# The_Flying_Jalapeno.net
KiCad netlist of a schematic drawn in EAGLE
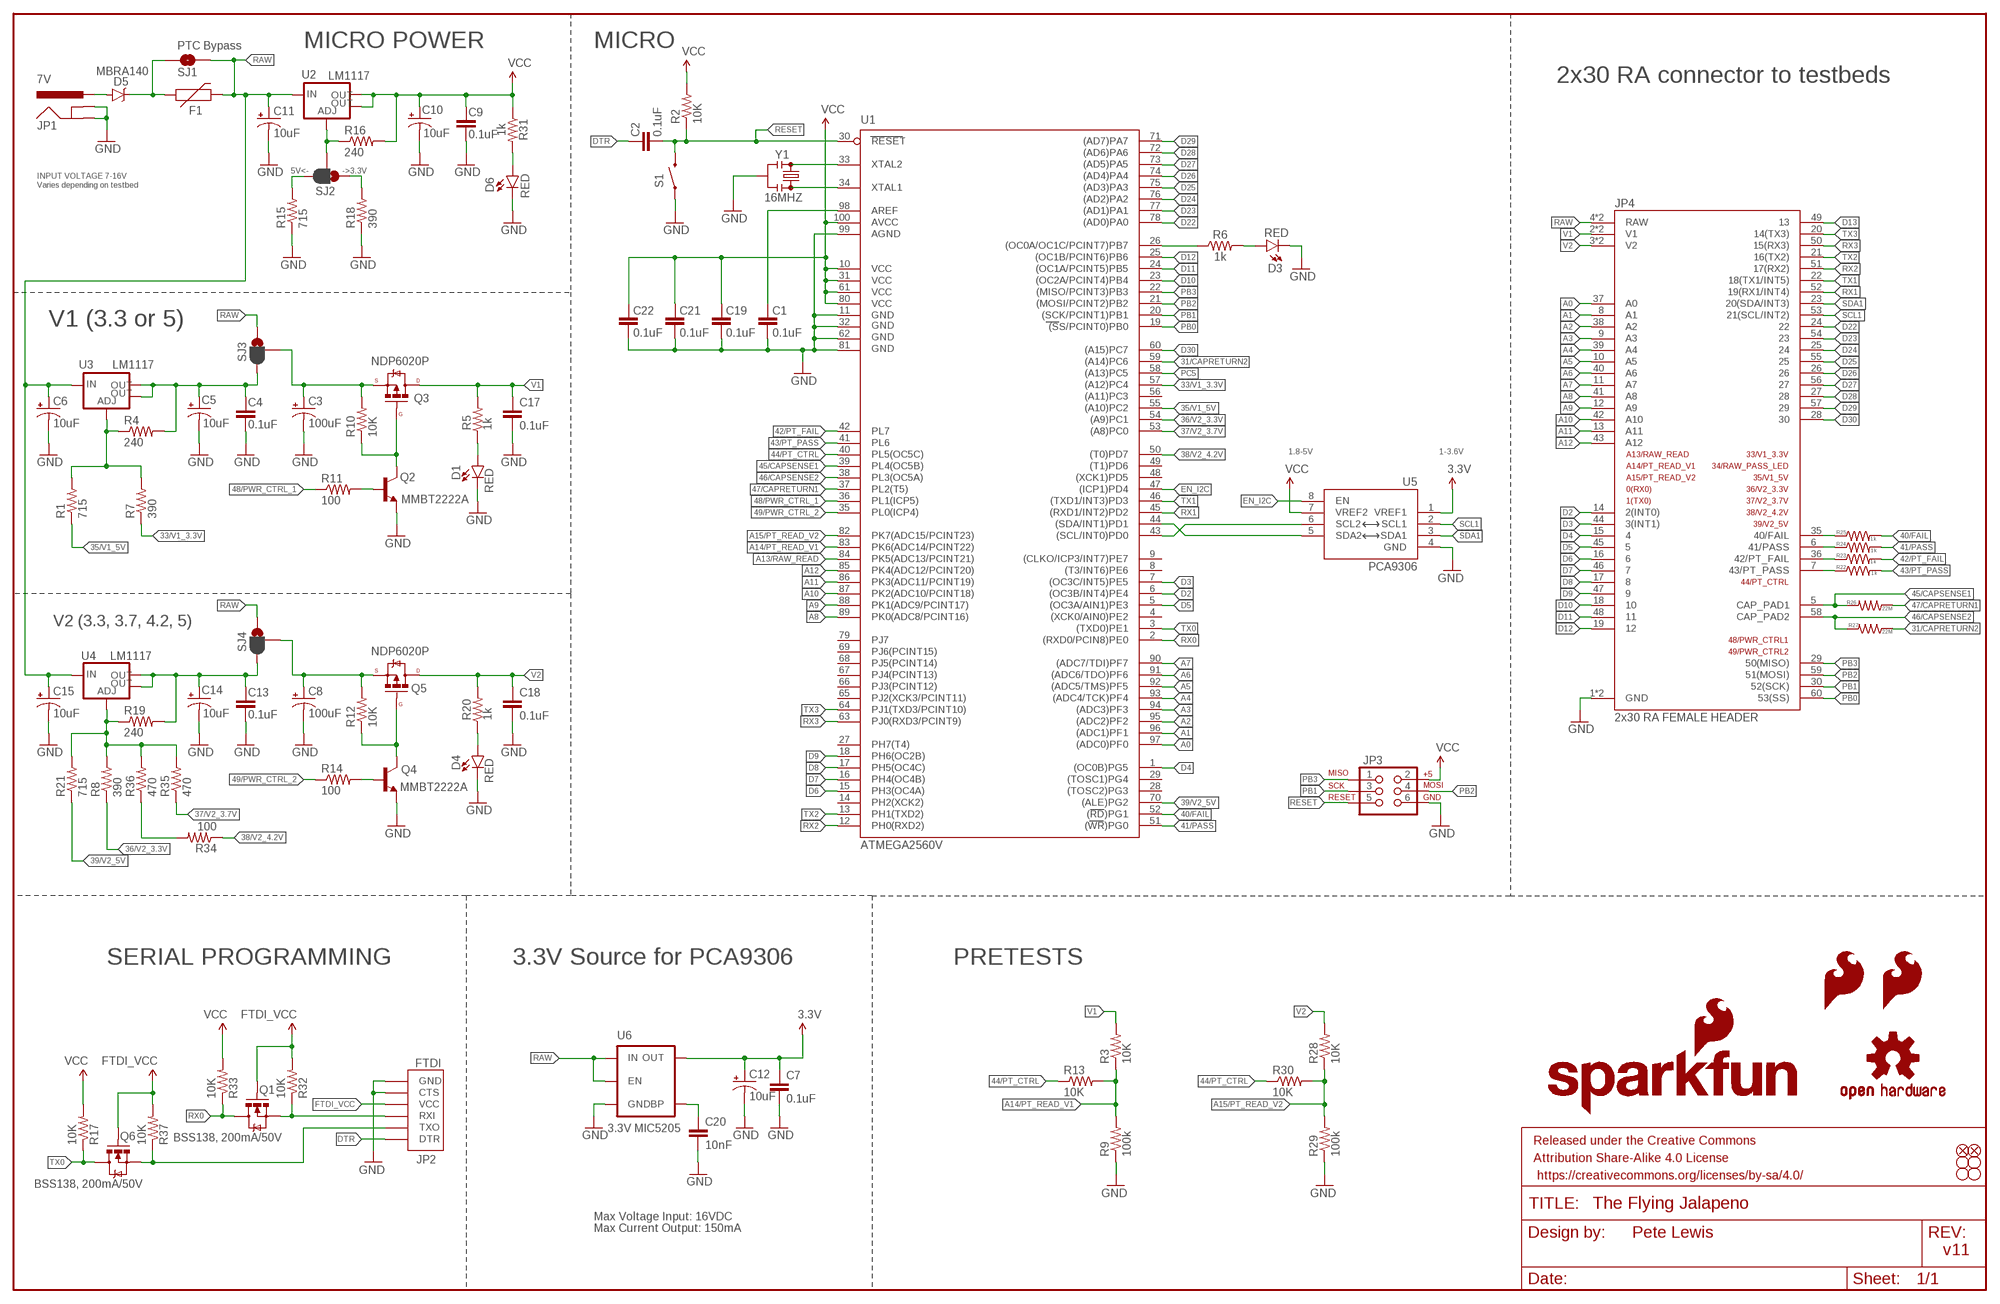
[diagram p0: schematic, sheet 1]

(export (version "E")
  (design (tool "Eeschema 10.0.6"))
  (components
    (comp (ref "C1")
      (value "0.1uF")
      (footprint "eagle-import:0603-CAP")
      (libsource (lib "eagle-import") (part "0.1UF-25V(+80/-20%)(0603)"))
    )
    (comp (ref "C2")
      (value "0.1uF")
      (footprint "eagle-import:0603-CAP")
      (libsource (lib "eagle-import") (part "0.1UF-25V(+80/-20%)(0603)"))
    )
    (comp (ref "C3")
      (value "100uF")
      (footprint "eagle-import:NIC_10X10.5_CAP")
      (libsource (lib "eagle-import") (part "100UF-63V-20%(ELECT)"))
    )
    (comp (ref "C4")
      (value "0.1uF")
      (footprint "eagle-import:0603-CAP")
      (libsource (lib "eagle-import") (part "0.1UF-25V(+80/-20%)(0603)"))
    )
    (comp (ref "C5")
      (value "10uF")
      (footprint "eagle-import:EIA3216")
      (libsource (lib "eagle-import") (part "10UF-16V-10%(TANT)"))
    )
    (comp (ref "C6")
      (value "10uF")
      (footprint "eagle-import:EIA3216")
      (libsource (lib "eagle-import") (part "10UF-16V-10%(TANT)"))
    )
    (comp (ref "C7")
      (value "0.1uF")
      (footprint "eagle-import:0603-CAP")
      (libsource (lib "eagle-import") (part "0.1UF-25V(+80/-20%)(0603)"))
    )
    (comp (ref "C8")
      (value "100uF")
      (footprint "eagle-import:NIC_10X10.5_CAP")
      (libsource (lib "eagle-import") (part "100UF-63V-20%(ELECT)"))
    )
    (comp (ref "C9")
      (value "0.1uF")
      (footprint "eagle-import:0603-CAP")
      (libsource (lib "eagle-import") (part "0.1UF-25V(+80/-20%)(0603)"))
    )
    (comp (ref "C10")
      (value "10uF")
      (footprint "eagle-import:EIA3216")
      (libsource (lib "eagle-import") (part "10UF-16V-10%(TANT)"))
    )
    (comp (ref "C11")
      (value "10uF")
      (footprint "eagle-import:EIA3216")
      (libsource (lib "eagle-import") (part "10UF-16V-10%(TANT)"))
    )
    (comp (ref "C12")
      (value "10uF")
      (footprint "eagle-import:0603-POL")
      (libsource (lib "eagle-import") (part "10UF-6.3V-20%(0603)(TANT){dblquote}"))
    )
    (comp (ref "C13")
      (value "0.1uF")
      (footprint "eagle-import:0603-CAP")
      (libsource (lib "eagle-import") (part "0.1UF-25V(+80/-20%)(0603)"))
    )
    (comp (ref "C14")
      (value "10uF")
      (footprint "eagle-import:EIA3216")
      (libsource (lib "eagle-import") (part "10UF-16V-10%(TANT)"))
    )
    (comp (ref "C15")
      (value "10uF")
      (footprint "eagle-import:EIA3216")
      (libsource (lib "eagle-import") (part "10UF-16V-10%(TANT)"))
    )
    (comp (ref "C17")
      (value "0.1uF")
      (footprint "eagle-import:0603-CAP")
      (libsource (lib "eagle-import") (part "0.1UF-25V(+80/-20%)(0603)"))
    )
    (comp (ref "C18")
      (value "0.1uF")
      (footprint "eagle-import:0603-CAP")
      (libsource (lib "eagle-import") (part "0.1UF-25V(+80/-20%)(0603)"))
    )
    (comp (ref "C19")
      (value "0.1uF")
      (footprint "eagle-import:0603-CAP")
      (libsource (lib "eagle-import") (part "0.1UF-25V(+80/-20%)(0603)"))
    )
    (comp (ref "C20")
      (value "10nF")
      (footprint "eagle-import:0603")
      (libsource (lib "eagle-import") (part "10NF-0603-50V-10%"))
    )
    (comp (ref "C21")
      (value "0.1uF")
      (footprint "eagle-import:0603-CAP")
      (libsource (lib "eagle-import") (part "0.1UF-25V(+80/-20%)(0603)"))
    )
    (comp (ref "C22")
      (value "0.1uF")
      (footprint "eagle-import:0603-CAP")
      (libsource (lib "eagle-import") (part "0.1UF-25V(+80/-20%)(0603)"))
    )
    (comp (ref "D1")
      (value "RED")
      (footprint "eagle-import:LED-1206")
      (libsource (lib "eagle-import") (part "LED-RED1206"))
    )
    (comp (ref "D3")
      (value "RED")
      (footprint "eagle-import:LED-1206")
      (libsource (lib "eagle-import") (part "LED-RED1206"))
    )
    (comp (ref "D4")
      (value "RED")
      (footprint "eagle-import:LED-1206")
      (libsource (lib "eagle-import") (part "LED-RED1206"))
    )
    (comp (ref "D5")
      (value "MBRA140")
      (footprint "eagle-import:SMA-DIODE")
      (libsource (lib "eagle-import") (part "DIODE-SCHOTTKY-MBRA140"))
    )
    (comp (ref "D6")
      (value "RED")
      (footprint "eagle-import:LED-1206")
      (libsource (lib "eagle-import") (part "LED-RED1206"))
    )
    (comp (ref "F1")
      (value "PTCTHERMISTOR1206")
      (footprint "eagle-import:PTC-1206")
      (libsource (lib "eagle-import") (part "PTCTHERMISTOR1206"))
    )
    (comp (ref "FRAME1")
      (value "FRAME-LEDGER")
      (footprint "eagle-import:CREATIVE_COMMONS")
      (libsource (lib "eagle-import") (part "FRAME-LEDGER"))
    )
    (comp (ref "JP1")
      (value "7V")
      (footprint "eagle-import:POWER_JACK_PTH_LOCK")
      (libsource (lib "eagle-import") (part "POWER_JACKPTH_LOCK"))
    )
    (comp (ref "JP2")
      (value "FTDI")
      (footprint "eagle-import:FTDI_DEVICE_RA_SMT")
      (libsource (lib "eagle-import") (part "FTDI_BASIC_DEVICE_SIDERA_SMT"))
    )
    (comp (ref "JP3")
      (value "AVR_SPI_PRG_6PTH")
      (footprint "eagle-import:2X3")
      (libsource (lib "eagle-import") (part "AVR_SPI_PRG_6PTH"))
    )
    (comp (ref "JP4")
      (value "2x30 RA FEMALE HEADER")
      (footprint "eagle-import:FLYING_JALAPENO_V3_F")
      (libsource (lib "eagle-import") (part "FLYING_JALAPENO_V3FEMALE"))
    )
    (comp (ref "JP5")
      (value "FIDUCIALUFIDUCIAL")
      (footprint "eagle-import:MICRO-FIDUCIAL")
      (libsource (lib "eagle-import") (part "FIDUCIALUFIDUCIAL"))
    )
    (comp (ref "JP8")
      (value "FIDUCIALUFIDUCIAL")
      (footprint "eagle-import:MICRO-FIDUCIAL")
      (libsource (lib "eagle-import") (part "FIDUCIALUFIDUCIAL"))
    )
    (comp (ref "LOGO1")
      (value "SFE_LOGO_NAME_FLAME.5_INCH")
      (footprint "eagle-import:SFE_LOGO_NAME_FLAME_.5")
      (libsource (lib "eagle-import") (part "SFE_LOGO_NAME_FLAME.5_INCH"))
    )
    (comp (ref "LOGO2")
      (value "SFE_LOGO_FLAME.3_INCH")
      (footprint "eagle-import:SFE_LOGO_FLAME_.3")
      (libsource (lib "eagle-import") (part "SFE_LOGO_FLAME.3_INCH"))
    )
    (comp (ref "LOGO3")
      (value "SFE_LOGO_FLAME.1_INCH")
      (footprint "eagle-import:SFE_LOGO_FLAME_.1")
      (libsource (lib "eagle-import") (part "SFE_LOGO_FLAME.1_INCH"))
    )
    (comp (ref "LOGO4")
      (value "OSHW-LOGOL")
      (footprint "eagle-import:OSHW-LOGO-L")
      (libsource (lib "eagle-import") (part "OSHW-LOGOL"))
    )
    (comp (ref "Q1")
      (value "BSS138, 200mA/50V")
      (footprint "eagle-import:SOT23-3")
      (libsource (lib "eagle-import") (part "MOSFET-NCHANNELBSS138"))
    )
    (comp (ref "Q2")
      (value "MMBT2222A")
      (footprint "eagle-import:SOT23-3")
      (libsource (lib "eagle-import") (part "TRANSISTOR_NPNMMBT2222A"))
    )
    (comp (ref "Q3")
      (value "NDP6020P")
      (footprint "eagle-import:TO220V")
      (libsource (lib "eagle-import") (part "MOSFET-PCHANNELNDP6020P_20V_24A_LOW_VGS_TH"))
    )
    (comp (ref "Q4")
      (value "MMBT2222A")
      (footprint "eagle-import:SOT23-3")
      (libsource (lib "eagle-import") (part "TRANSISTOR_NPNMMBT2222A"))
    )
    (comp (ref "Q5")
      (value "NDP6020P")
      (footprint "eagle-import:TO220V")
      (libsource (lib "eagle-import") (part "MOSFET-PCHANNELNDP6020P_20V_24A_LOW_VGS_TH"))
    )
    (comp (ref "Q6")
      (value "BSS138, 200mA/50V")
      (footprint "eagle-import:SOT23-3")
      (libsource (lib "eagle-import") (part "MOSFET-NCHANNELBSS138"))
    )
    (comp (ref "R1")
      (value "715")
      (footprint "eagle-import:0603-RES")
      (libsource (lib "eagle-import") (part "715OHM1/10W1%(0603)"))
    )
    (comp (ref "R2")
      (value "10K")
      (footprint "eagle-import:0603-RES")
      (libsource (lib "eagle-import") (part "10KOHM-1/10W-1%(0603)0603"))
    )
    (comp (ref "R3")
      (value "10K")
      (footprint "eagle-import:0603-RES")
      (libsource (lib "eagle-import") (part "10KOHM-1/10W-1%(0603)0603"))
    )
    (comp (ref "R4")
      (value "240")
      (footprint "eagle-import:0603-RES")
      (libsource (lib "eagle-import") (part "240OHM1/10W1%(0603)"))
    )
    (comp (ref "R5")
      (value "1k")
      (footprint "eagle-import:0603")
      (libsource (lib "eagle-import") (part "1KOHM-0603-1/10W-1%"))
    )
    (comp (ref "R6")
      (value "1k")
      (footprint "eagle-import:0603")
      (libsource (lib "eagle-import") (part "1KOHM-0603-1/10W-1%"))
    )
    (comp (ref "R7")
      (value "390")
      (footprint "eagle-import:0603-RES")
      (libsource (lib "eagle-import") (part "390OHM1/10W1%(0603)"))
    )
    (comp (ref "R8")
      (value "390")
      (footprint "eagle-import:0603-RES")
      (libsource (lib "eagle-import") (part "390OHM1/10W1%(0603)"))
    )
    (comp (ref "R9")
      (value "100k")
      (footprint "eagle-import:0603-RES")
      (libsource (lib "eagle-import") (part "100KOHM-1/10W-1%(0603)"))
    )
    (comp (ref "R10")
      (value "10K")
      (footprint "eagle-import:0603-RES")
      (libsource (lib "eagle-import") (part "10KOHM-1/10W-1%(0603)0603"))
    )
    (comp (ref "R11")
      (value "100")
      (footprint "eagle-import:0603-RES")
      (libsource (lib "eagle-import") (part "100OHM-1/10W-1%(0603)"))
    )
    (comp (ref "R12")
      (value "10K")
      (footprint "eagle-import:0603-RES")
      (libsource (lib "eagle-import") (part "10KOHM-1/10W-1%(0603)0603"))
    )
    (comp (ref "R13")
      (value "10K")
      (footprint "eagle-import:0603-RES")
      (libsource (lib "eagle-import") (part "10KOHM-1/10W-1%(0603)0603"))
    )
    (comp (ref "R14")
      (value "100")
      (footprint "eagle-import:0603-RES")
      (libsource (lib "eagle-import") (part "100OHM-1/10W-1%(0603)"))
    )
    (comp (ref "R15")
      (value "715")
      (footprint "eagle-import:0603-RES")
      (libsource (lib "eagle-import") (part "715OHM1/10W1%(0603)"))
    )
    (comp (ref "R16")
      (value "240")
      (footprint "eagle-import:0603-RES")
      (libsource (lib "eagle-import") (part "240OHM1/10W1%(0603)"))
    )
    (comp (ref "R17")
      (value "10K")
      (footprint "eagle-import:0603-RES")
      (libsource (lib "eagle-import") (part "10KOHM-1/10W-1%(0603)0603"))
    )
    (comp (ref "R18")
      (value "390")
      (footprint "eagle-import:0603-RES")
      (libsource (lib "eagle-import") (part "390OHM1/10W1%(0603)"))
    )
    (comp (ref "R19")
      (value "240")
      (footprint "eagle-import:0603-RES")
      (libsource (lib "eagle-import") (part "240OHM1/10W1%(0603)"))
    )
    (comp (ref "R20")
      (value "1k")
      (footprint "eagle-import:0603")
      (libsource (lib "eagle-import") (part "1KOHM-0603-1/10W-1%"))
    )
    (comp (ref "R21")
      (value "715")
      (footprint "eagle-import:0603-RES")
      (libsource (lib "eagle-import") (part "715OHM1/10W1%(0603)"))
    )
    (comp (ref "R22")
      (value "1k")
      (footprint "eagle-import:0603")
      (libsource (lib "eagle-import") (part "1KOHM-0603-1/10W-1%"))
    )
    (comp (ref "R23")
      (value "1k")
      (footprint "eagle-import:0603")
      (libsource (lib "eagle-import") (part "1KOHM-0603-1/10W-1%"))
    )
    (comp (ref "R24")
      (value "1k")
      (footprint "eagle-import:0603")
      (libsource (lib "eagle-import") (part "1KOHM-0603-1/10W-1%"))
    )
    (comp (ref "R25")
      (value "1k")
      (footprint "eagle-import:0603")
      (libsource (lib "eagle-import") (part "1KOHM-0603-1/10W-1%"))
    )
    (comp (ref "R26")
      (value "22M")
      (footprint "eagle-import:0603-RES")
      (libsource (lib "eagle-import") (part "22MOHM-1/10W-10%(0603)"))
    )
    (comp (ref "R27")
      (value "22M")
      (footprint "eagle-import:0603-RES")
      (libsource (lib "eagle-import") (part "22MOHM-1/10W-10%(0603)"))
    )
    (comp (ref "R28")
      (value "10K")
      (footprint "eagle-import:0603-RES")
      (libsource (lib "eagle-import") (part "10KOHM-1/10W-1%(0603)0603"))
    )
    (comp (ref "R29")
      (value "100k")
      (footprint "eagle-import:0603-RES")
      (libsource (lib "eagle-import") (part "100KOHM-1/10W-1%(0603)"))
    )
    (comp (ref "R30")
      (value "10K")
      (footprint "eagle-import:0603-RES")
      (libsource (lib "eagle-import") (part "10KOHM-1/10W-1%(0603)0603"))
    )
    (comp (ref "R31")
      (value "1k")
      (footprint "eagle-import:0603")
      (libsource (lib "eagle-import") (part "1KOHM-0603-1/10W-1%"))
    )
    (comp (ref "R32")
      (value "10K")
      (footprint "eagle-import:0603-RES")
      (libsource (lib "eagle-import") (part "10KOHM-1/10W-1%(0603)0603"))
    )
    (comp (ref "R33")
      (value "10K")
      (footprint "eagle-import:0603-RES")
      (libsource (lib "eagle-import") (part "10KOHM-1/10W-1%(0603)0603"))
    )
    (comp (ref "R34")
      (value "100")
      (footprint "eagle-import:0603-RES")
      (libsource (lib "eagle-import") (part "100OHM-1/10W-1%(0603)"))
    )
    (comp (ref "R35")
      (value "470")
      (footprint "eagle-import:0603-RES")
      (libsource (lib "eagle-import") (part "470OHM1/10W1%(0603)"))
    )
    (comp (ref "R36")
      (value "470")
      (footprint "eagle-import:0603-RES")
      (libsource (lib "eagle-import") (part "470OHM1/10W1%(0603)"))
    )
    (comp (ref "R37")
      (value "10K")
      (footprint "eagle-import:0603-RES")
      (libsource (lib "eagle-import") (part "10KOHM-1/10W-1%(0603)0603"))
    )
    (comp (ref "S1")
      (value "SWITCH-MOMENTARY-2SMD-REDUNDANT")
      (footprint "eagle-import:TACTILE-SWITCH-SMD")
      (libsource (lib "eagle-import") (part "SWITCH-MOMENTARY-2SMD-REDUNDANT"))
    )
    (comp (ref "SJ1")
      (value "PTC Bypass")
      (footprint "eagle-import:PAD-JUMPER-2-NO_NO_SILK")
      (libsource (lib "eagle-import") (part "JUMPER-PAD-2-NO"))
    )
    (comp (ref "SJ2")
      (value "JUMPER-PAD-3-2OF3_NC_BY_PASTE")
      (footprint "eagle-import:PAD-JUMPER-3-2OF3_NC_BY_PASTE_YES_SILK_FULL_BOX")
      (libsource (lib "eagle-import") (part "JUMPER-PAD-3-2OF3_NC_BY_PASTE"))
    )
    (comp (ref "SJ3")
      (value "JUMPER-PAD-3-2OF3_NC_BY_PASTE")
      (footprint "eagle-import:PAD-JUMPER-3-2OF3_NC_BY_PASTE_YES_SILK_FULL_BOX")
      (libsource (lib "eagle-import") (part "JUMPER-PAD-3-2OF3_NC_BY_PASTE"))
    )
    (comp (ref "SJ4")
      (value "JUMPER-PAD-3-2OF3_NC_BY_PASTE")
      (footprint "eagle-import:PAD-JUMPER-3-2OF3_NC_BY_PASTE_YES_SILK_FULL_BOX")
      (libsource (lib "eagle-import") (part "JUMPER-PAD-3-2OF3_NC_BY_PASTE"))
    )
    (comp (ref "STANDOFF1")
      (value "STAND-OFFTIGHT")
      (footprint "eagle-import:STAND-OFF-TIGHT")
      (libsource (lib "eagle-import") (part "STAND-OFFTIGHT"))
    )
    (comp (ref "STANDOFF2")
      (value "STAND-OFFTIGHT")
      (footprint "eagle-import:STAND-OFF-TIGHT")
      (libsource (lib "eagle-import") (part "STAND-OFFTIGHT"))
    )
    (comp (ref "STANDOFF3")
      (value "STAND-OFFTIGHT")
      (footprint "eagle-import:STAND-OFF-TIGHT")
      (libsource (lib "eagle-import") (part "STAND-OFFTIGHT"))
    )
    (comp (ref "STANDOFF4")
      (value "STAND-OFFTIGHT")
      (footprint "eagle-import:STAND-OFF-TIGHT")
      (libsource (lib "eagle-import") (part "STAND-OFFTIGHT"))
    )
    (comp (ref "U1")
      (value "ATMEGA2560AU")
      (footprint "eagle-import:TQFP100")
      (libsource (lib "eagle-import") (part "ATMEGA2560AU"))
    )
    (comp (ref "U2")
      (value "LM1117")
      (footprint "eagle-import:SOT223")
      (libsource (lib "eagle-import") (part "V_REG_LM1117SOT223"))
    )
    (comp (ref "U3")
      (value "LM1117")
      (footprint "eagle-import:SOT223")
      (libsource (lib "eagle-import") (part "V_REG_LM1117SOT223"))
    )
    (comp (ref "U4")
      (value "LM1117")
      (footprint "eagle-import:SOT223")
      (libsource (lib "eagle-import") (part "V_REG_LM1117SOT223"))
    )
    (comp (ref "U5")
      (value "PCA9306")
      (footprint "eagle-import:PCA9306DC-1_1")
      (libsource (lib "eagle-import") (part "PCA9306PCA9306DC-1{colon}1"))
    )
    (comp (ref "U6")
      (value "3.3V MIC5205")
      (footprint "eagle-import:SOT23-5")
      (libsource (lib "eagle-import") (part "MIC52053.3V"))
    )
    (comp (ref "Y1")
      (value "16MHZ")
      (footprint "eagle-import:RESONATOR-SMD")
      (libsource (lib "eagle-import") (part "RESONATOR16MHZ"))
    )
  )
  (nets
    (net (code "1") (name "3.3V") (class "Default")
      (node (ref "C12") (pin "A") (pinfunction "+_A") (pintype "passive"))
      (node (ref "C7") (pin "1") (pinfunction "1_1") (pintype "passive"))
      (node (ref "U5") (pin "1") (pinfunction "VREF1_1") (pintype "bidirectional"))
      (node (ref "U6") (pin "5") (pinfunction "OUT_5") (pintype "passive"))
    )
    (net (code "2") (name "31{slash}CAPRETURN2") (class "Default")
      (node (ref "R27") (pin "1") (pinfunction "1_1") (pintype "passive"))
      (node (ref "U1") (pin "59") (pinfunction "(A14)PC6_59") (pintype "bidirectional"))
    )
    (net (code "3") (name "33{slash}V1_3.3V") (class "Default")
      (node (ref "R7") (pin "1") (pinfunction "1_1") (pintype "passive"))
      (node (ref "U1") (pin "57") (pinfunction "(A12)PC4_57") (pintype "bidirectional"))
    )
    (net (code "4") (name "35{slash}V1_5V") (class "Default")
      (node (ref "R1") (pin "1") (pinfunction "1_1") (pintype "passive"))
      (node (ref "U1") (pin "55") (pinfunction "(A10)PC2_55") (pintype "bidirectional"))
    )
    (net (code "5") (name "36{slash}V2_3.3V") (class "Default")
      (node (ref "R8") (pin "1") (pinfunction "1_1") (pintype "passive"))
      (node (ref "U1") (pin "54") (pinfunction "(A9)PC1_54") (pintype "bidirectional"))
    )
    (net (code "6") (name "37{slash}V2_3.7V") (class "Default")
      (node (ref "R35") (pin "1") (pinfunction "1_1") (pintype "passive"))
      (node (ref "U1") (pin "53") (pinfunction "(A8)PC0_53") (pintype "bidirectional"))
    )
    (net (code "7") (name "38{slash}V2_4.2V") (class "Default")
      (node (ref "R34") (pin "1") (pinfunction "1_1") (pintype "passive"))
      (node (ref "U1") (pin "50") (pinfunction "(T0)PD7_50") (pintype "bidirectional"))
    )
    (net (code "8") (name "39{slash}V2_5V") (class "Default")
      (node (ref "R21") (pin "1") (pinfunction "1_1") (pintype "passive"))
      (node (ref "U1") (pin "70") (pinfunction "(ALE)PG2_70") (pintype "bidirectional"))
    )
    (net (code "9") (name "40{slash}FAIL") (class "Default")
      (node (ref "R25") (pin "2") (pinfunction "2_2") (pintype "passive"))
      (node (ref "U1") (pin "52") (pinfunction "(RD)PG1_52") (pintype "bidirectional"))
    )
    (net (code "10") (name "41{slash}PASS") (class "Default")
      (node (ref "R24") (pin "2") (pinfunction "2_2") (pintype "passive"))
      (node (ref "U1") (pin "51") (pinfunction "(WR)PG0_51") (pintype "bidirectional"))
    )
    (net (code "11") (name "42{slash}PT_FAIL") (class "Default")
      (node (ref "R23") (pin "2") (pinfunction "2_2") (pintype "passive"))
      (node (ref "U1") (pin "42") (pinfunction "PL7_42") (pintype "bidirectional"))
    )
    (net (code "12") (name "43{slash}PT_PASS") (class "Default")
      (node (ref "R22") (pin "2") (pinfunction "2_2") (pintype "passive"))
      (node (ref "U1") (pin "41") (pinfunction "PL6_41") (pintype "bidirectional"))
    )
    (net (code "13") (name "44{slash}PT_CTRL") (class "Default")
      (node (ref "R13") (pin "1") (pinfunction "1_1") (pintype "passive"))
      (node (ref "R30") (pin "1") (pinfunction "1_1") (pintype "passive"))
      (node (ref "U1") (pin "40") (pinfunction "PL5(OC5C)_40") (pintype "bidirectional"))
    )
    (net (code "14") (name "45{slash}CAPSENSE1") (class "Default")
      (node (ref "JP4") (pin "5") (pinfunction "CAP_PAD1_5") (pintype "bidirectional"))
      (node (ref "R26") (pin "2") (pinfunction "2_2") (pintype "passive"))
      (node (ref "U1") (pin "39") (pinfunction "PL4(OC5B)_39") (pintype "bidirectional"))
    )
    (net (code "15") (name "46{slash}CAPSENSE2") (class "Default")
      (node (ref "JP4") (pin "58") (pinfunction "CAP_PAD2_58") (pintype "bidirectional"))
      (node (ref "R27") (pin "2") (pinfunction "2_2") (pintype "passive"))
      (node (ref "U1") (pin "38") (pinfunction "PL3(OC5A)_38") (pintype "bidirectional"))
    )
    (net (code "16") (name "47{slash}CAPRETURN1") (class "Default")
      (node (ref "R26") (pin "1") (pinfunction "1_1") (pintype "passive"))
      (node (ref "U1") (pin "37") (pinfunction "PL2(T5)_37") (pintype "bidirectional"))
    )
    (net (code "17") (name "48{slash}PWR_CTRL_1") (class "Default")
      (node (ref "R11") (pin "1") (pinfunction "1_1") (pintype "passive"))
      (node (ref "U1") (pin "36") (pinfunction "PL1(ICP5)_36") (pintype "bidirectional"))
    )
    (net (code "18") (name "49{slash}PWR_CTRL_2") (class "Default")
      (node (ref "R14") (pin "1") (pinfunction "1_1") (pintype "passive"))
      (node (ref "U1") (pin "35") (pinfunction "PL0(ICP4)_35") (pintype "bidirectional"))
    )
    (net (code "19") (name "A0") (class "Default")
      (node (ref "JP4") (pin "37") (pinfunction "A0_37") (pintype "bidirectional"))
      (node (ref "U1") (pin "97") (pinfunction "(ADC0)PF0_97") (pintype "bidirectional"))
    )
    (net (code "20") (name "A1") (class "Default")
      (node (ref "JP4") (pin "8") (pinfunction "A1_8") (pintype "bidirectional"))
      (node (ref "U1") (pin "96") (pinfunction "(ADC1)PF1_96") (pintype "bidirectional"))
    )
    (net (code "21") (name "A2") (class "Default")
      (node (ref "JP4") (pin "38") (pinfunction "A2_38") (pintype "bidirectional"))
      (node (ref "U1") (pin "95") (pinfunction "(ADC2)PF2_95") (pintype "bidirectional"))
    )
    (net (code "22") (name "A3") (class "Default")
      (node (ref "JP4") (pin "9") (pinfunction "A3_9") (pintype "bidirectional"))
      (node (ref "U1") (pin "94") (pinfunction "(ADC3)PF3_94") (pintype "bidirectional"))
    )
    (net (code "23") (name "A4") (class "Default")
      (node (ref "JP4") (pin "39") (pinfunction "A4_39") (pintype "bidirectional"))
      (node (ref "U1") (pin "93") (pinfunction "(ADC4/TCK)PF4_93") (pintype "bidirectional"))
    )
    (net (code "24") (name "A5") (class "Default")
      (node (ref "JP4") (pin "10") (pinfunction "A5_10") (pintype "bidirectional"))
      (node (ref "U1") (pin "92") (pinfunction "(ADC5/TMS)PF5_92") (pintype "bidirectional"))
    )
    (net (code "25") (name "A6") (class "Default")
      (node (ref "JP4") (pin "40") (pinfunction "A6_40") (pintype "bidirectional"))
      (node (ref "U1") (pin "91") (pinfunction "(ADC6/TDO)PF6_91") (pintype "bidirectional"))
    )
    (net (code "26") (name "A7") (class "Default")
      (node (ref "JP4") (pin "11") (pinfunction "A7_11") (pintype "bidirectional"))
      (node (ref "U1") (pin "90") (pinfunction "(ADC7/TDI)PF7_90") (pintype "bidirectional"))
    )
    (net (code "27") (name "A8") (class "Default")
      (node (ref "JP4") (pin "41") (pinfunction "A8_41") (pintype "bidirectional"))
      (node (ref "U1") (pin "89") (pinfunction "PK0(ADC8/PCINT16)_89") (pintype "bidirectional"))
    )
    (net (code "28") (name "A9") (class "Default")
      (node (ref "JP4") (pin "12") (pinfunction "A9_12") (pintype "bidirectional"))
      (node (ref "U1") (pin "88") (pinfunction "PK1(ADC9/PCINT17)_88") (pintype "bidirectional"))
    )
    (net (code "29") (name "A10") (class "Default")
      (node (ref "JP4") (pin "42") (pinfunction "A10_42") (pintype "bidirectional"))
      (node (ref "U1") (pin "87") (pinfunction "PK2(ADC10/PCINT18)_87") (pintype "bidirectional"))
    )
    (net (code "30") (name "A11") (class "Default")
      (node (ref "JP4") (pin "13") (pinfunction "A11_13") (pintype "bidirectional"))
      (node (ref "U1") (pin "86") (pinfunction "PK3(ADC11/PCINT19)_86") (pintype "bidirectional"))
    )
    (net (code "31") (name "A12") (class "Default")
      (node (ref "JP4") (pin "43") (pinfunction "A12_43") (pintype "bidirectional"))
      (node (ref "U1") (pin "85") (pinfunction "PK4(ADC12/PCINT20)_85") (pintype "bidirectional"))
    )
    (net (code "32") (name "A13{slash}RAW_READ") (class "Default")
      (node (ref "U1") (pin "84") (pinfunction "PK5(ADC13/PCINT21)_84") (pintype "bidirectional"))
    )
    (net (code "33") (name "A14{slash}PT_READ_V1") (class "Default")
      (node (ref "R13") (pin "2") (pinfunction "2_2") (pintype "passive"))
      (node (ref "R3") (pin "1") (pinfunction "1_1") (pintype "passive"))
      (node (ref "R9") (pin "2") (pinfunction "2_2") (pintype "passive"))
      (node (ref "U1") (pin "83") (pinfunction "PK6(ADC14/PCINT22)_83") (pintype "bidirectional"))
    )
    (net (code "34") (name "A15{slash}PT_READ_V2") (class "Default")
      (node (ref "R28") (pin "1") (pinfunction "1_1") (pintype "passive"))
      (node (ref "R29") (pin "2") (pinfunction "2_2") (pintype "passive"))
      (node (ref "R30") (pin "2") (pinfunction "2_2") (pintype "passive"))
      (node (ref "U1") (pin "82") (pinfunction "PK7(ADC15/PCINT23)_82") (pintype "bidirectional"))
    )
    (net (code "35") (name "D2") (class "Default")
      (node (ref "JP4") (pin "14") (pinfunction "2(INT0)_14") (pintype "bidirectional"))
      (node (ref "U1") (pin "6") (pinfunction "(OC3B/INT4)PE4_6") (pintype "bidirectional"))
    )
    (net (code "36") (name "D3") (class "Default")
      (node (ref "JP4") (pin "44") (pinfunction "3(INT1)_44") (pintype "bidirectional"))
      (node (ref "U1") (pin "7") (pinfunction "(OC3C/INT5)PE5_7") (pintype "bidirectional"))
    )
    (net (code "37") (name "D4") (class "Default")
      (node (ref "JP4") (pin "15") (pinfunction "4_15") (pintype "bidirectional"))
      (node (ref "U1") (pin "1") (pinfunction "(OC0B)PG5_1") (pintype "bidirectional"))
    )
    (net (code "38") (name "D5") (class "Default")
      (node (ref "JP4") (pin "45") (pinfunction "5_45") (pintype "bidirectional"))
      (node (ref "U1") (pin "5") (pinfunction "(OC3A/AIN1)PE3_5") (pintype "bidirectional"))
    )
    (net (code "39") (name "D6") (class "Default")
      (node (ref "JP4") (pin "16") (pinfunction "6_16") (pintype "bidirectional"))
      (node (ref "U1") (pin "15") (pinfunction "PH3(OC4A)_15") (pintype "bidirectional"))
    )
    (net (code "40") (name "D7") (class "Default")
      (node (ref "JP4") (pin "46") (pinfunction "7_46") (pintype "bidirectional"))
      (node (ref "U1") (pin "16") (pinfunction "PH4(OC4B)_16") (pintype "bidirectional"))
    )
    (net (code "41") (name "D8") (class "Default")
      (node (ref "JP4") (pin "17") (pinfunction "8_17") (pintype "bidirectional"))
      (node (ref "U1") (pin "17") (pinfunction "PH5(OC4C)_17") (pintype "bidirectional"))
    )
    (net (code "42") (name "D9") (class "Default")
      (node (ref "JP4") (pin "47") (pinfunction "9_47") (pintype "bidirectional"))
      (node (ref "U1") (pin "18") (pinfunction "PH6(OC2B)_18") (pintype "bidirectional"))
    )
    (net (code "43") (name "D10") (class "Default")
      (node (ref "JP4") (pin "18") (pinfunction "10_18") (pintype "bidirectional"))
      (node (ref "U1") (pin "23") (pinfunction "(OC2A/PCINT4)PB4_23") (pintype "bidirectional"))
    )
    (net (code "44") (name "D11") (class "Default")
      (node (ref "JP4") (pin "48") (pinfunction "11_48") (pintype "bidirectional"))
      (node (ref "U1") (pin "24") (pinfunction "(OC1A/PCINT5)PB5_24") (pintype "bidirectional"))
    )
    (net (code "45") (name "D12") (class "Default")
      (node (ref "JP4") (pin "19") (pinfunction "12_19") (pintype "bidirectional"))
      (node (ref "U1") (pin "25") (pinfunction "(OC1B/PCINT6)PB6_25") (pintype "bidirectional"))
    )
    (net (code "46") (name "D13") (class "Default")
      (node (ref "JP4") (pin "49") (pinfunction "13_49") (pintype "bidirectional"))
      (node (ref "R6") (pin "1") (pinfunction "1_1") (pintype "passive"))
      (node (ref "U1") (pin "26") (pinfunction "(OC0A/OC1C/PCINT7)PB7_26") (pintype "bidirectional"))
    )
    (net (code "47") (name "D22") (class "Default")
      (node (ref "JP4") (pin "24") (pinfunction "22_24") (pintype "bidirectional"))
      (node (ref "U1") (pin "78") (pinfunction "(AD0)PA0_78") (pintype "bidirectional"))
    )
    (net (code "48") (name "D23") (class "Default")
      (node (ref "JP4") (pin "54") (pinfunction "23_54") (pintype "bidirectional"))
      (node (ref "U1") (pin "77") (pinfunction "(AD1)PA1_77") (pintype "bidirectional"))
    )
    (net (code "49") (name "D24") (class "Default")
      (node (ref "JP4") (pin "25") (pinfunction "24_25") (pintype "bidirectional"))
      (node (ref "U1") (pin "76") (pinfunction "(AD2)PA2_76") (pintype "bidirectional"))
    )
    (net (code "50") (name "D25") (class "Default")
      (node (ref "JP4") (pin "55") (pinfunction "25_55") (pintype "bidirectional"))
      (node (ref "U1") (pin "75") (pinfunction "(AD3)PA3_75") (pintype "bidirectional"))
    )
    (net (code "51") (name "D26") (class "Default")
      (node (ref "JP4") (pin "26") (pinfunction "26_26") (pintype "bidirectional"))
      (node (ref "U1") (pin "74") (pinfunction "(AD4)PA4_74") (pintype "bidirectional"))
    )
    (net (code "52") (name "D27") (class "Default")
      (node (ref "JP4") (pin "56") (pinfunction "27_56") (pintype "bidirectional"))
      (node (ref "U1") (pin "73") (pinfunction "(AD5)PA5_73") (pintype "bidirectional"))
    )
    (net (code "53") (name "D28") (class "Default")
      (node (ref "JP4") (pin "27") (pinfunction "28_27") (pintype "bidirectional"))
      (node (ref "U1") (pin "72") (pinfunction "(AD6)PA6_72") (pintype "bidirectional"))
    )
    (net (code "54") (name "D29") (class "Default")
      (node (ref "JP4") (pin "57") (pinfunction "29_57") (pintype "bidirectional"))
      (node (ref "U1") (pin "71") (pinfunction "(AD7)PA7_71") (pintype "bidirectional"))
    )
    (net (code "55") (name "D30") (class "Default")
      (node (ref "JP4") (pin "28") (pinfunction "30_28") (pintype "bidirectional"))
      (node (ref "U1") (pin "60") (pinfunction "(A15)PC7_60") (pintype "bidirectional"))
    )
    (net (code "56") (name "DTR") (class "Default")
      (node (ref "C2") (pin "2") (pinfunction "2_2") (pintype "passive"))
      (node (ref "JP2") (pin "1") (pinfunction "DTR_1") (pintype "bidirectional"))
    )
    (net (code "57") (name "EN_I2C") (class "Default")
      (node (ref "U1") (pin "47") (pinfunction "(ICP1)PD4_47") (pintype "bidirectional"))
      (node (ref "U5") (pin "8") (pinfunction "EN_8") (pintype "bidirectional"))
    )
    (net (code "58") (name "FTDI_VCC") (class "Default")
      (node (ref "JP2") (pin "4") (pinfunction "VCC_4") (pintype "bidirectional"))
      (node (ref "Q1") (pin "1") (pinfunction "G_1") (pintype "passive"))
      (node (ref "Q6") (pin "1") (pinfunction "G_1") (pintype "passive"))
      (node (ref "R32") (pin "2") (pinfunction "2_2") (pintype "passive"))
      (node (ref "R37") (pin "2") (pinfunction "2_2") (pintype "passive"))
    )
    (net (code "59") (name "GND") (class "Default")
      (node (ref "C1") (pin "1") (pinfunction "1_1") (pintype "passive"))
      (node (ref "C10") (pin "C") (pinfunction "-_C") (pintype "passive"))
      (node (ref "C11") (pin "C") (pinfunction "-_C") (pintype "passive"))
      (node (ref "C12") (pin "K") (pinfunction "-_K") (pintype "passive"))
      (node (ref "C13") (pin "2") (pinfunction "2_2") (pintype "passive"))
      (node (ref "C14") (pin "C") (pinfunction "-_C") (pintype "passive"))
      (node (ref "C15") (pin "C") (pinfunction "-_C") (pintype "passive"))
      (node (ref "C17") (pin "2") (pinfunction "2_2") (pintype "passive"))
      (node (ref "C18") (pin "2") (pinfunction "2_2") (pintype "passive"))
      (node (ref "C19") (pin "1") (pinfunction "1_1") (pintype "passive"))
      (node (ref "C20") (pin "2") (pinfunction "2_2") (pintype "passive"))
      (node (ref "C21") (pin "1") (pinfunction "1_1") (pintype "passive"))
      (node (ref "C22") (pin "1") (pinfunction "1_1") (pintype "passive"))
      (node (ref "C3") (pin "-") (pinfunction "-_-") (pintype "passive"))
      (node (ref "C4") (pin "2") (pinfunction "2_2") (pintype "passive"))
      (node (ref "C5") (pin "C") (pinfunction "-_C") (pintype "passive"))
      (node (ref "C6") (pin "C") (pinfunction "-_C") (pintype "passive"))
      (node (ref "C7") (pin "2") (pinfunction "2_2") (pintype "passive"))
      (node (ref "C8") (pin "-") (pinfunction "-_-") (pintype "passive"))
      (node (ref "C9") (pin "2") (pinfunction "2_2") (pintype "passive"))
      (node (ref "D1") (pin "C") (pinfunction "C_C") (pintype "passive"))
      (node (ref "D3") (pin "C") (pinfunction "C_C") (pintype "passive"))
      (node (ref "D4") (pin "C") (pinfunction "C_C") (pintype "passive"))
      (node (ref "D6") (pin "C") (pinfunction "C_C") (pintype "passive"))
      (node (ref "JP1") (pin "GND") (pinfunction "GND_GND") (pintype "bidirectional"))
      (node (ref "JP1") (pin "GNDBREAK") (pinfunction "GNDBREAK_GNDBREAK") (pintype "bidirectional"))
      (node (ref "JP2") (pin "5") (pinfunction "CTS_5") (pintype "bidirectional"))
      (node (ref "JP2") (pin "6") (pinfunction "GND_6") (pintype "bidirectional"))
      (node (ref "JP3") (pin "6") (pinfunction "6_6") (pintype "passive"))
      (node (ref "JP4") (pin "1") (pinfunction "GND_1") (pintype "bidirectional"))
      (node (ref "JP4") (pin "31") (pinfunction "GND_31") (pintype "bidirectional"))
      (node (ref "Q2") (pin "2") (pinfunction "E_2") (pintype "passive"))
      (node (ref "Q4") (pin "2") (pinfunction "E_2") (pintype "passive"))
      (node (ref "R15") (pin "1") (pinfunction "1_1") (pintype "passive"))
      (node (ref "R18") (pin "1") (pinfunction "1_1") (pintype "passive"))
      (node (ref "R29") (pin "1") (pinfunction "1_1") (pintype "passive"))
      (node (ref "R9") (pin "1") (pinfunction "1_1") (pintype "passive"))
      (node (ref "S1") (pin "1") (pinfunction "1_1") (pintype "passive"))
      (node (ref "S1") (pin "2") (pinfunction "1_2") (pintype "passive"))
      (node (ref "U1") (pin "11") (pinfunction "GND_11") (pintype "power_in"))
      (node (ref "U1") (pin "32") (pinfunction "GND1_32") (pintype "power_in"))
      (node (ref "U1") (pin "62") (pinfunction "GND2_62") (pintype "power_in"))
      (node (ref "U1") (pin "81") (pinfunction "GND3_81") (pintype "power_in"))
      (node (ref "U1") (pin "99") (pinfunction "AGND_99") (pintype "power_in"))
      (node (ref "U5") (pin "4") (pinfunction "GND_4") (pintype "bidirectional"))
      (node (ref "U6") (pin "2") (pinfunction "GND_2") (pintype "input"))
      (node (ref "Y1") (pin "2") (pinfunction "2_2") (pintype "passive"))
    )
    (net (code "60") (name "Net-(C5-+)") (class "Default")
      (node (ref "C4") (pin "1") (pinfunction "1_1") (pintype "passive"))
      (node (ref "C5") (pin "A") (pinfunction "+_A") (pintype "passive"))
      (node (ref "R4") (pin "2") (pinfunction "2_2") (pintype "passive"))
      (node (ref "SJ3") (pin "3") (pinfunction "3_3") (pintype "passive"))
      (node (ref "U3") (pin "2") (pinfunction "OUT_2") (pintype "output"))
      (node (ref "U3") (pin "4") (pinfunction "OUT_4") (pintype "output"))
    )
    (net (code "61") (name "Net-(C14-+)") (class "Default")
      (node (ref "C13") (pin "1") (pinfunction "1_1") (pintype "passive"))
      (node (ref "C14") (pin "A") (pinfunction "+_A") (pintype "passive"))
      (node (ref "R19") (pin "2") (pinfunction "2_2") (pintype "passive"))
      (node (ref "SJ4") (pin "3") (pinfunction "3_3") (pintype "passive"))
      (node (ref "U4") (pin "2") (pinfunction "OUT_2") (pintype "output"))
      (node (ref "U4") (pin "4") (pinfunction "OUT_4") (pintype "output"))
    )
    (net (code "62") (name "Net-(D1-PadA)") (class "Default")
      (node (ref "D1") (pin "A") (pinfunction "A_A") (pintype "passive"))
      (node (ref "R5") (pin "1") (pinfunction "1_1") (pintype "passive"))
    )
    (net (code "63") (name "Net-(D3-PadA)") (class "Default")
      (node (ref "D3") (pin "A") (pinfunction "A_A") (pintype "passive"))
      (node (ref "R6") (pin "2") (pinfunction "2_2") (pintype "passive"))
    )
    (net (code "64") (name "Net-(D4-PadA)") (class "Default")
      (node (ref "D4") (pin "A") (pinfunction "A_A") (pintype "passive"))
      (node (ref "R20") (pin "1") (pinfunction "1_1") (pintype "passive"))
    )
    (net (code "65") (name "Net-(D5-PadA)") (class "Default")
      (node (ref "D5") (pin "A") (pinfunction "A_A") (pintype "passive"))
      (node (ref "JP1") (pin "PWR") (pinfunction "PWR_PWR") (pintype "bidirectional"))
    )
    (net (code "66") (name "Net-(D5-PadC)") (class "Default")
      (node (ref "D5") (pin "C") (pinfunction "C_C") (pintype "passive"))
      (node (ref "F1") (pin "1") (pinfunction "1_1") (pintype "bidirectional"))
      (node (ref "SJ1") (pin "1") (pinfunction "1_1") (pintype "passive"))
    )
    (net (code "67") (name "Net-(D6-PadA)") (class "Default")
      (node (ref "D6") (pin "A") (pinfunction "A_A") (pintype "passive"))
      (node (ref "R31") (pin "2") (pinfunction "2_2") (pintype "passive"))
    )
    (net (code "68") (name "Net-(JP2-RXI)") (class "Default")
      (node (ref "JP2") (pin "3") (pinfunction "RXI_3") (pintype "bidirectional"))
      (node (ref "Q1") (pin "2") (pinfunction "S_2") (pintype "passive"))
      (node (ref "R32") (pin "1") (pinfunction "1_1") (pintype "passive"))
    )
    (net (code "69") (name "Net-(JP2-TXO)") (class "Default")
      (node (ref "JP2") (pin "2") (pinfunction "TXO_2") (pintype "bidirectional"))
      (node (ref "Q6") (pin "2") (pinfunction "S_2") (pintype "passive"))
      (node (ref "R37") (pin "1") (pinfunction "1_1") (pintype "passive"))
    )
    (net (code "70") (name "Net-(JP4-40{slash}FAIL)") (class "Default")
      (node (ref "JP4") (pin "35") (pinfunction "40/FAIL_35") (pintype "bidirectional"))
      (node (ref "R25") (pin "1") (pinfunction "1_1") (pintype "passive"))
    )
    (net (code "71") (name "Net-(JP4-41{slash}PASS)") (class "Default")
      (node (ref "JP4") (pin "6") (pinfunction "41/PASS_6") (pintype "bidirectional"))
      (node (ref "R24") (pin "1") (pinfunction "1_1") (pintype "passive"))
    )
    (net (code "72") (name "Net-(JP4-42{slash}PT_FAIL)") (class "Default")
      (node (ref "JP4") (pin "36") (pinfunction "42/PT_FAIL_36") (pintype "bidirectional"))
      (node (ref "R23") (pin "1") (pinfunction "1_1") (pintype "passive"))
    )
    (net (code "73") (name "Net-(JP4-43{slash}PT_PASS)") (class "Default")
      (node (ref "JP4") (pin "7") (pinfunction "43/PT_PASS_7") (pintype "bidirectional"))
      (node (ref "R22") (pin "1") (pinfunction "1_1") (pintype "passive"))
    )
    (net (code "74") (name "Net-(Q2-B)") (class "Default")
      (node (ref "Q2") (pin "1") (pinfunction "B_1") (pintype "passive"))
      (node (ref "R11") (pin "2") (pinfunction "2_2") (pintype "passive"))
    )
    (net (code "75") (name "Net-(Q2-C)") (class "Default")
      (node (ref "Q2") (pin "3") (pinfunction "C_3") (pintype "passive"))
      (node (ref "Q3") (pin "1") (pinfunction "G_1") (pintype "passive"))
      (node (ref "R10") (pin "1") (pinfunction "1_1") (pintype "passive"))
    )
    (net (code "76") (name "Net-(Q3-S)") (class "Default")
      (node (ref "C3") (pin "+") (pinfunction "+_+") (pintype "passive"))
      (node (ref "Q3") (pin "3") (pinfunction "S_3") (pintype "passive"))
      (node (ref "R10") (pin "2") (pinfunction "2_2") (pintype "passive"))
      (node (ref "SJ3") (pin "2") (pinfunction "2_2") (pintype "passive"))
    )
    (net (code "77") (name "Net-(Q4-B)") (class "Default")
      (node (ref "Q4") (pin "1") (pinfunction "B_1") (pintype "passive"))
      (node (ref "R14") (pin "2") (pinfunction "2_2") (pintype "passive"))
    )
    (net (code "78") (name "Net-(Q4-C)") (class "Default")
      (node (ref "Q4") (pin "3") (pinfunction "C_3") (pintype "passive"))
      (node (ref "Q5") (pin "1") (pinfunction "G_1") (pintype "passive"))
      (node (ref "R12") (pin "1") (pinfunction "1_1") (pintype "passive"))
    )
    (net (code "79") (name "Net-(Q5-S)") (class "Default")
      (node (ref "C8") (pin "+") (pinfunction "+_+") (pintype "passive"))
      (node (ref "Q5") (pin "3") (pinfunction "S_3") (pintype "passive"))
      (node (ref "R12") (pin "2") (pinfunction "2_2") (pintype "passive"))
      (node (ref "SJ4") (pin "2") (pinfunction "2_2") (pintype "passive"))
    )
    (net (code "80") (name "Net-(R15-Pad2)") (class "Default")
      (node (ref "R15") (pin "2") (pinfunction "2_2") (pintype "passive"))
      (node (ref "SJ2") (pin "3") (pinfunction "3_3") (pintype "passive"))
    )
    (net (code "81") (name "Net-(R18-Pad2)") (class "Default")
      (node (ref "R18") (pin "2") (pinfunction "2_2") (pintype "passive"))
      (node (ref "SJ2") (pin "1") (pinfunction "1_1") (pintype "passive"))
    )
    (net (code "82") (name "Net-(R34-Pad2)") (class "Default")
      (node (ref "R34") (pin "2") (pinfunction "2_2") (pintype "passive"))
      (node (ref "R36") (pin "1") (pinfunction "1_1") (pintype "passive"))
    )
    (net (code "83") (name "Net-(U1-(SCL{slash}INT0)PD0)") (class "Default")
      (node (ref "U1") (pin "43") (pinfunction "(SCL/INT0)PD0_43") (pintype "bidirectional"))
      (node (ref "U5") (pin "6") (pinfunction "SCL2_6") (pintype "bidirectional"))
    )
    (net (code "84") (name "Net-(U1-(SDA{slash}INT1)PD1)") (class "Default")
      (node (ref "U1") (pin "44") (pinfunction "(SDA/INT1)PD1_44") (pintype "bidirectional"))
      (node (ref "U5") (pin "5") (pinfunction "SDA2_5") (pintype "bidirectional"))
    )
    (net (code "85") (name "Net-(U1-AREF)") (class "Default")
      (node (ref "C1") (pin "2") (pinfunction "2_2") (pintype "passive"))
      (node (ref "U1") (pin "98") (pinfunction "AREF_98") (pintype "bidirectional"))
    )
    (net (code "86") (name "Net-(U1-XTAL1)") (class "Default")
      (node (ref "U1") (pin "34") (pinfunction "XTAL1_34") (pintype "input"))
      (node (ref "Y1") (pin "1") (pinfunction "1_1") (pintype "passive"))
    )
    (net (code "87") (name "Net-(U1-XTAL2)") (class "Default")
      (node (ref "U1") (pin "33") (pinfunction "XTAL2_33") (pintype "output"))
      (node (ref "Y1") (pin "3") (pinfunction "3_3") (pintype "passive"))
    )
    (net (code "88") (name "Net-(U2-ADJ)") (class "Default")
      (node (ref "R16") (pin "1") (pinfunction "1_1") (pintype "passive"))
      (node (ref "SJ2") (pin "2") (pinfunction "2_2") (pintype "passive"))
      (node (ref "U2") (pin "1") (pinfunction "ADJ_1") (pintype "input"))
    )
    (net (code "89") (name "Net-(U3-ADJ)") (class "Default")
      (node (ref "R1") (pin "2") (pinfunction "2_2") (pintype "passive"))
      (node (ref "R4") (pin "1") (pinfunction "1_1") (pintype "passive"))
      (node (ref "R7") (pin "2") (pinfunction "2_2") (pintype "passive"))
      (node (ref "U3") (pin "1") (pinfunction "ADJ_1") (pintype "input"))
    )
    (net (code "90") (name "Net-(U4-ADJ)") (class "Default")
      (node (ref "R19") (pin "1") (pinfunction "1_1") (pintype "passive"))
      (node (ref "R21") (pin "2") (pinfunction "2_2") (pintype "passive"))
      (node (ref "R35") (pin "2") (pinfunction "2_2") (pintype "passive"))
      (node (ref "R36") (pin "2") (pinfunction "2_2") (pintype "passive"))
      (node (ref "R8") (pin "2") (pinfunction "2_2") (pintype "passive"))
      (node (ref "U4") (pin "1") (pinfunction "ADJ_1") (pintype "input"))
    )
    (net (code "91") (name "Net-(U6-BP)") (class "Default")
      (node (ref "C20") (pin "1") (pinfunction "1_1") (pintype "passive"))
      (node (ref "U6") (pin "4") (pinfunction "BP_4") (pintype "input"))
    )
    (net (code "92") (name "PB0") (class "Default")
      (node (ref "JP4") (pin "60") (pinfunction "53(SS)_60") (pintype "bidirectional"))
      (node (ref "U1") (pin "19") (pinfunction "(SS/PCINT0)PB0_19") (pintype "bidirectional"))
    )
    (net (code "93") (name "PB1") (class "Default")
      (node (ref "JP3") (pin "3") (pinfunction "3_3") (pintype "passive"))
      (node (ref "JP4") (pin "30") (pinfunction "52(SCK)_30") (pintype "bidirectional"))
      (node (ref "U1") (pin "20") (pinfunction "(SCK/PCINT1)PB1_20") (pintype "bidirectional"))
    )
    (net (code "94") (name "PB2") (class "Default")
      (node (ref "JP3") (pin "4") (pinfunction "4_4") (pintype "passive"))
      (node (ref "JP4") (pin "59") (pinfunction "51(MOSI)_59") (pintype "bidirectional"))
      (node (ref "U1") (pin "21") (pinfunction "(MOSI/PCINT2)PB2_21") (pintype "bidirectional"))
    )
    (net (code "95") (name "PB3") (class "Default")
      (node (ref "JP3") (pin "1") (pinfunction "1_1") (pintype "passive"))
      (node (ref "JP4") (pin "29") (pinfunction "50(MISO)_29") (pintype "bidirectional"))
      (node (ref "U1") (pin "22") (pinfunction "(MISO/PCINT3)PB3_22") (pintype "bidirectional"))
    )
    (net (code "96") (name "PC5") (class "Default")
      (node (ref "U1") (pin "58") (pinfunction "(A13)PC5_58") (pintype "bidirectional"))
    )
    (net (code "97") (name "RAW") (class "Default")
      (node (ref "C11") (pin "A") (pinfunction "+_A") (pintype "passive"))
      (node (ref "C15") (pin "A") (pinfunction "+_A") (pintype "passive"))
      (node (ref "C6") (pin "A") (pinfunction "+_A") (pintype "passive"))
      (node (ref "F1") (pin "2") (pinfunction "2_2") (pintype "bidirectional"))
      (node (ref "JP4") (pin "34") (pinfunction "RAW_34") (pintype "bidirectional"))
      (node (ref "JP4") (pin "4") (pinfunction "RAW_4") (pintype "bidirectional"))
      (node (ref "SJ1") (pin "2") (pinfunction "2_2") (pintype "passive"))
      (node (ref "SJ3") (pin "1") (pinfunction "1_1") (pintype "passive"))
      (node (ref "SJ4") (pin "1") (pinfunction "1_1") (pintype "passive"))
      (node (ref "U2") (pin "3") (pinfunction "IN_3") (pintype "input"))
      (node (ref "U3") (pin "3") (pinfunction "IN_3") (pintype "input"))
      (node (ref "U4") (pin "3") (pinfunction "IN_3") (pintype "input"))
      (node (ref "U6") (pin "1") (pinfunction "IN_1") (pintype "input"))
      (node (ref "U6") (pin "3") (pinfunction "EN_3") (pintype "input"))
    )
    (net (code "98") (name "RESET") (class "Default")
      (node (ref "C2") (pin "1") (pinfunction "1_1") (pintype "passive"))
      (node (ref "JP3") (pin "5") (pinfunction "5_5") (pintype "passive"))
      (node (ref "R2") (pin "1") (pinfunction "1_1") (pintype "passive"))
      (node (ref "S1") (pin "3") (pinfunction "2_3") (pintype "passive"))
      (node (ref "S1") (pin "4") (pinfunction "2_4") (pintype "passive"))
      (node (ref "U1") (pin "30") (pinfunction "RESET_30") (pintype "input"))
    )
    (net (code "99") (name "RX0") (class "Default")
      (node (ref "Q1") (pin "3") (pinfunction "D_3") (pintype "passive"))
      (node (ref "R33") (pin "1") (pinfunction "1_1") (pintype "passive"))
      (node (ref "U1") (pin "2") (pinfunction "(RXD0/PCIN8)PE0_2") (pintype "bidirectional"))
    )
    (net (code "100") (name "RX1") (class "Default")
      (node (ref "JP4") (pin "52") (pinfunction "19(RX1/INT4)_52") (pintype "bidirectional"))
      (node (ref "U1") (pin "45") (pinfunction "(RXD1/INT2)PD2_45") (pintype "bidirectional"))
    )
    (net (code "101") (name "RX2") (class "Default")
      (node (ref "JP4") (pin "51") (pinfunction "17(RX2)_51") (pintype "bidirectional"))
      (node (ref "U1") (pin "12") (pinfunction "PH0(RXD2)_12") (pintype "bidirectional"))
    )
    (net (code "102") (name "RX3") (class "Default")
      (node (ref "JP4") (pin "50") (pinfunction "15(RX3)_50") (pintype "bidirectional"))
      (node (ref "U1") (pin "63") (pinfunction "PJ0(RXD3/PCINT9)_63") (pintype "bidirectional"))
    )
    (net (code "103") (name "SCL1") (class "Default")
      (node (ref "JP4") (pin "53") (pinfunction "21(SCL/INT2)_53") (pintype "bidirectional"))
      (node (ref "U5") (pin "2") (pinfunction "SCL1_2") (pintype "bidirectional"))
    )
    (net (code "104") (name "SDA1") (class "Default")
      (node (ref "JP4") (pin "23") (pinfunction "20(SDA/INT3)_23") (pintype "bidirectional"))
      (node (ref "U5") (pin "3") (pinfunction "SDA1_3") (pintype "bidirectional"))
    )
    (net (code "105") (name "TX0") (class "Default")
      (node (ref "Q6") (pin "3") (pinfunction "D_3") (pintype "passive"))
      (node (ref "R17") (pin "1") (pinfunction "1_1") (pintype "passive"))
      (node (ref "U1") (pin "3") (pinfunction "(TXD0)PE1_3") (pintype "bidirectional"))
    )
    (net (code "106") (name "TX1") (class "Default")
      (node (ref "JP4") (pin "22") (pinfunction "18(TX1/INT5)_22") (pintype "bidirectional"))
      (node (ref "U1") (pin "46") (pinfunction "(TXD1/INT3)PD3_46") (pintype "bidirectional"))
    )
    (net (code "107") (name "TX2") (class "Default")
      (node (ref "JP4") (pin "21") (pinfunction "16(TX2)_21") (pintype "bidirectional"))
      (node (ref "U1") (pin "13") (pinfunction "PH1(TXD2)_13") (pintype "bidirectional"))
    )
    (net (code "108") (name "TX3") (class "Default")
      (node (ref "JP4") (pin "20") (pinfunction "14(TX3)_20") (pintype "bidirectional"))
      (node (ref "U1") (pin "64") (pinfunction "PJ1(TXD3/PCINT10)_64") (pintype "bidirectional"))
    )
    (net (code "109") (name "V1") (class "Default")
      (node (ref "C17") (pin "1") (pinfunction "1_1") (pintype "passive"))
      (node (ref "JP4") (pin "2") (pinfunction "V1_2") (pintype "bidirectional"))
      (node (ref "JP4") (pin "32") (pinfunction "V1_32") (pintype "bidirectional"))
      (node (ref "Q3") (pin "2") (pinfunction "D_2") (pintype "passive"))
      (node (ref "R3") (pin "2") (pinfunction "2_2") (pintype "passive"))
      (node (ref "R5") (pin "2") (pinfunction "2_2") (pintype "passive"))
    )
    (net (code "110") (name "V2") (class "Default")
      (node (ref "C18") (pin "1") (pinfunction "1_1") (pintype "passive"))
      (node (ref "JP4") (pin "3") (pinfunction "V2_3") (pintype "bidirectional"))
      (node (ref "JP4") (pin "33") (pinfunction "V2_33") (pintype "bidirectional"))
      (node (ref "Q5") (pin "2") (pinfunction "D_2") (pintype "passive"))
      (node (ref "R20") (pin "2") (pinfunction "2_2") (pintype "passive"))
      (node (ref "R28") (pin "2") (pinfunction "2_2") (pintype "passive"))
    )
    (net (code "111") (name "VCC") (class "Default")
      (node (ref "C10") (pin "A") (pinfunction "+_A") (pintype "passive"))
      (node (ref "C19") (pin "2") (pinfunction "2_2") (pintype "passive"))
      (node (ref "C21") (pin "2") (pinfunction "2_2") (pintype "passive"))
      (node (ref "C22") (pin "2") (pinfunction "2_2") (pintype "passive"))
      (node (ref "C9") (pin "1") (pinfunction "1_1") (pintype "passive"))
      (node (ref "JP3") (pin "2") (pinfunction "2_2") (pintype "passive"))
      (node (ref "R16") (pin "2") (pinfunction "2_2") (pintype "passive"))
      (node (ref "R17") (pin "2") (pinfunction "2_2") (pintype "passive"))
      (node (ref "R2") (pin "2") (pinfunction "2_2") (pintype "passive"))
      (node (ref "R31") (pin "1") (pinfunction "1_1") (pintype "passive"))
      (node (ref "R33") (pin "2") (pinfunction "2_2") (pintype "passive"))
      (node (ref "U1") (pin "10") (pinfunction "VCC_10") (pintype "power_in"))
      (node (ref "U1") (pin "100") (pinfunction "AVCC_100") (pintype "power_in"))
      (node (ref "U1") (pin "31") (pinfunction "VCC1_31") (pintype "power_in"))
      (node (ref "U1") (pin "61") (pinfunction "VCC2_61") (pintype "power_in"))
      (node (ref "U1") (pin "80") (pinfunction "VCC3_80") (pintype "power_in"))
      (node (ref "U2") (pin "2") (pinfunction "OUT_2") (pintype "output"))
      (node (ref "U2") (pin "4") (pinfunction "OUT_4") (pintype "output"))
      (node (ref "U5") (pin "7") (pinfunction "VREF2_7") (pintype "bidirectional"))
    )
    (net (code "112") (name "unconnected-(U1-(A11)PC3-Pad56)") (class "Default")
      (node (ref "U1") (pin "56") (pinfunction "(A11)PC3_56") (pintype "bidirectional"))
    )
    (net (code "113") (name "unconnected-(U1-(CLKO{slash}ICP3{slash}INT7)PE7-Pad9)") (class "Default")
      (node (ref "U1") (pin "9") (pinfunction "(CLKO/ICP3/INT7)PE7_9") (pintype "bidirectional"))
    )
    (net (code "114") (name "unconnected-(U1-(T1)PD6-Pad49)") (class "Default")
      (node (ref "U1") (pin "49") (pinfunction "(T1)PD6_49") (pintype "bidirectional"))
    )
    (net (code "115") (name "unconnected-(U1-(T3{slash}INT6)PE6-Pad8)") (class "Default")
      (node (ref "U1") (pin "8") (pinfunction "(T3/INT6)PE6_8") (pintype "bidirectional"))
    )
    (net (code "116") (name "unconnected-(U1-(TOSC1)PG4-Pad29)") (class "Default")
      (node (ref "U1") (pin "29") (pinfunction "(TOSC1)PG4_29") (pintype "bidirectional"))
    )
    (net (code "117") (name "unconnected-(U1-(TOSC2)PG3-Pad28)") (class "Default")
      (node (ref "U1") (pin "28") (pinfunction "(TOSC2)PG3_28") (pintype "bidirectional"))
    )
    (net (code "118") (name "unconnected-(U1-(XCK0{slash}AIN0)PE2-Pad4)") (class "Default")
      (node (ref "U1") (pin "4") (pinfunction "(XCK0/AIN0)PE2_4") (pintype "bidirectional"))
    )
    (net (code "119") (name "unconnected-(U1-(XCK1)PD5-Pad48)") (class "Default")
      (node (ref "U1") (pin "48") (pinfunction "(XCK1)PD5_48") (pintype "bidirectional"))
    )
    (net (code "120") (name "unconnected-(U1-PH2(XCK2)-Pad14)") (class "Default")
      (node (ref "U1") (pin "14") (pinfunction "PH2(XCK2)_14") (pintype "bidirectional"))
    )
    (net (code "121") (name "unconnected-(U1-PH7(T4)-Pad27)") (class "Default")
      (node (ref "U1") (pin "27") (pinfunction "PH7(T4)_27") (pintype "bidirectional"))
    )
    (net (code "122") (name "unconnected-(U1-PJ2(XCK3{slash}PCINT11)-Pad65)") (class "Default")
      (node (ref "U1") (pin "65") (pinfunction "PJ2(XCK3/PCINT11)_65") (pintype "bidirectional"))
    )
    (net (code "123") (name "unconnected-(U1-PJ3(PCINT12)-Pad66)") (class "Default")
      (node (ref "U1") (pin "66") (pinfunction "PJ3(PCINT12)_66") (pintype "bidirectional"))
    )
    (net (code "124") (name "unconnected-(U1-PJ4(PCINT13)-Pad67)") (class "Default")
      (node (ref "U1") (pin "67") (pinfunction "PJ4(PCINT13)_67") (pintype "bidirectional"))
    )
    (net (code "125") (name "unconnected-(U1-PJ5(PCINT14)-Pad68)") (class "Default")
      (node (ref "U1") (pin "68") (pinfunction "PJ5(PCINT14)_68") (pintype "bidirectional"))
    )
    (net (code "126") (name "unconnected-(U1-PJ6(PCINT15)-Pad69)") (class "Default")
      (node (ref "U1") (pin "69") (pinfunction "PJ6(PCINT15)_69") (pintype "bidirectional"))
    )
    (net (code "127") (name "unconnected-(U1-PJ7-Pad79)") (class "Default")
      (node (ref "U1") (pin "79") (pinfunction "PJ7_79") (pintype "bidirectional"))
    )
  )
)
